# FM-Super-Regen.net
KiCad netlist of a schematic drawn in EAGLE
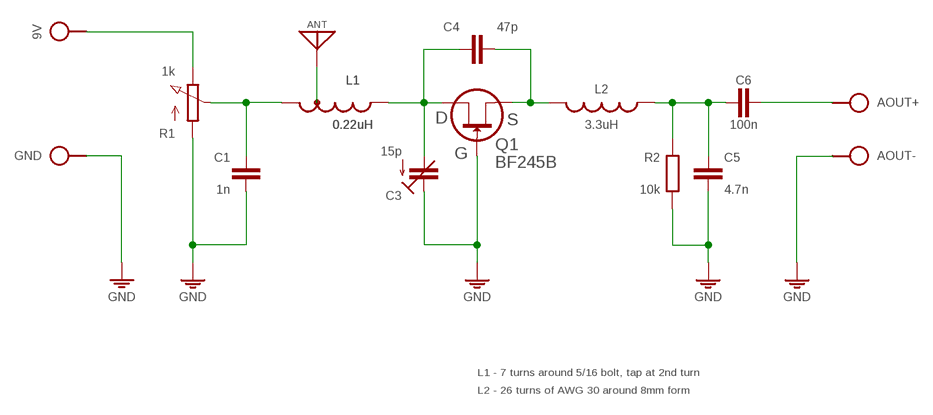
[diagram p0: schematic, sheet 1]

(export (version "E")
  (design (tool "Eeschema 10.0.6"))
  (components
    (comp (ref "9V")
      (value "SPAD")
      (footprint "eagle-import:SPAD")
      (libsource (lib "eagle-import") (part "SPAD"))
    )
    (comp (ref "ANT")
      (value "ANT")
      (footprint "eagle-import:SPAD")
      (libsource (lib "eagle-import") (part "ANT"))
    )
    (comp (ref "AOUT+")
      (value "SPAD")
      (footprint "eagle-import:SPAD")
      (libsource (lib "eagle-import") (part "SPAD"))
    )
    (comp (ref "AOUT-")
      (value "SPAD")
      (footprint "eagle-import:SPAD")
      (libsource (lib "eagle-import") (part "SPAD"))
    )
    (comp (ref "C1")
      (value "1n")
      (footprint "eagle-import:C050-020X036_V")
      (libsource (lib "eagle-import") (part "C050-020X036/V"))
    )
    (comp (ref "C3")
      (value "15p")
      (footprint "eagle-import:TRIM-2222-808")
      (libsource (lib "eagle-import") (part "C-TR-PH201272222-808-2PIN"))
    )
    (comp (ref "C4")
      (value "47p")
      (footprint "eagle-import:C025-015X024")
      (libsource (lib "eagle-import") (part "C025-015X024"))
    )
    (comp (ref "C5")
      (value "4.7n")
      (footprint "eagle-import:C050-020X036")
      (libsource (lib "eagle-import") (part "C050-020X036"))
    )
    (comp (ref "C6")
      (value "100n")
      (footprint "eagle-import:C050-020X036")
      (libsource (lib "eagle-import") (part "C050-020X036"))
    )
    (comp (ref "GND")
      (value "SPAD")
      (footprint "eagle-import:SPAD")
      (libsource (lib "eagle-import") (part "SPAD"))
    )
    (comp (ref "L1")
      (value "0.22uH")
      (footprint "eagle-import:L-08_7V-TAP1")
      (libsource (lib "eagle-import") (part "L-TAP108/7V"))
    )
    (comp (ref "L2")
      (value "3.3uH")
      (footprint "eagle-import:L-BODY")
      (libsource (lib "eagle-import") (part "L-BODY"))
    )
    (comp (ref "Q1")
      (value "BF245B")
      (footprint "eagle-import:TO92")
      (libsource (lib "eagle-import") (part "BF245B"))
    )
    (comp (ref "R1")
      (value "1k")
      (footprint "eagle-import:POT-V")
      (libsource (lib "eagle-import") (part "POT-V"))
    )
    (comp (ref "R2")
      (value "10k")
      (footprint "eagle-import:0204_10")
      (libsource (lib "eagle-import") (part "R0204/10"))
    )
  )
  (nets
    (net (code "1") (name "GND") (class "Default")
      (node (ref "AOUT-") (pin "1") (pinfunction "P$1_1") (pintype "bidirectional"))
      (node (ref "C1") (pin "2") (pinfunction "2_2") (pintype "passive"))
      (node (ref "C3") (pin "1") (pinfunction "E_1") (pintype "passive"))
      (node (ref "C5") (pin "2") (pinfunction "2_2") (pintype "passive"))
      (node (ref "GND") (pin "1") (pinfunction "P$1_1") (pintype "bidirectional"))
      (node (ref "Q1") (pin "1") (pinfunction "G_1") (pintype "passive"))
      (node (ref "R1") (pin "A") (pinfunction "A_A") (pintype "passive"))
      (node (ref "R2") (pin "1") (pinfunction "1_1") (pintype "passive"))
    )
    (net (code "2") (name "Net-(9V-P$1)") (class "Default")
      (node (ref "9V") (pin "1") (pinfunction "P$1_1") (pintype "bidirectional"))
      (node (ref "R1") (pin "E") (pinfunction "E_E") (pintype "passive"))
    )
    (net (code "3") (name "Net-(ANT-Pad1)") (class "Default")
      (node (ref "ANT") (pin "1") (pinfunction "1_1") (pintype "output"))
      (node (ref "L1") (pin "T") (pinfunction "T_T") (pintype "passive"))
    )
    (net (code "4") (name "Net-(AOUT+-P$1)") (class "Default")
      (node (ref "AOUT+") (pin "1") (pinfunction "P$1_1") (pintype "bidirectional"))
      (node (ref "C6") (pin "2") (pinfunction "2_2") (pintype "passive"))
    )
    (net (code "5") (name "Net-(C1-Pad1)") (class "Default")
      (node (ref "C1") (pin "1") (pinfunction "1_1") (pintype "passive"))
      (node (ref "L1") (pin "1") (pinfunction "1_1") (pintype "passive"))
      (node (ref "R1") (pin "S") (pinfunction "S_S") (pintype "passive"))
    )
    (net (code "6") (name "Net-(C3-A)") (class "Default")
      (node (ref "C3") (pin "2") (pinfunction "A_2") (pintype "passive"))
      (node (ref "C4") (pin "1") (pinfunction "1_1") (pintype "passive"))
      (node (ref "L1") (pin "2") (pinfunction "2_2") (pintype "passive"))
      (node (ref "Q1") (pin "3") (pinfunction "D_3") (pintype "passive"))
    )
    (net (code "7") (name "Net-(L2-1)") (class "Default")
      (node (ref "C5") (pin "1") (pinfunction "1_1") (pintype "passive"))
      (node (ref "C6") (pin "1") (pinfunction "1_1") (pintype "passive"))
      (node (ref "L2") (pin "4") (pinfunction "1_4") (pintype "passive"))
      (node (ref "R2") (pin "2") (pinfunction "2_2") (pintype "passive"))
    )
    (net (code "8") (name "Net-(L2-2)") (class "Default")
      (node (ref "C4") (pin "2") (pinfunction "2_2") (pintype "passive"))
      (node (ref "L2") (pin "3") (pinfunction "2_3") (pintype "passive"))
      (node (ref "Q1") (pin "2") (pinfunction "S_2") (pintype "passive"))
    )
  )
)
